# FPGA_-_Copy.net
KiCad netlist of a schematic drawn in Altium Designer
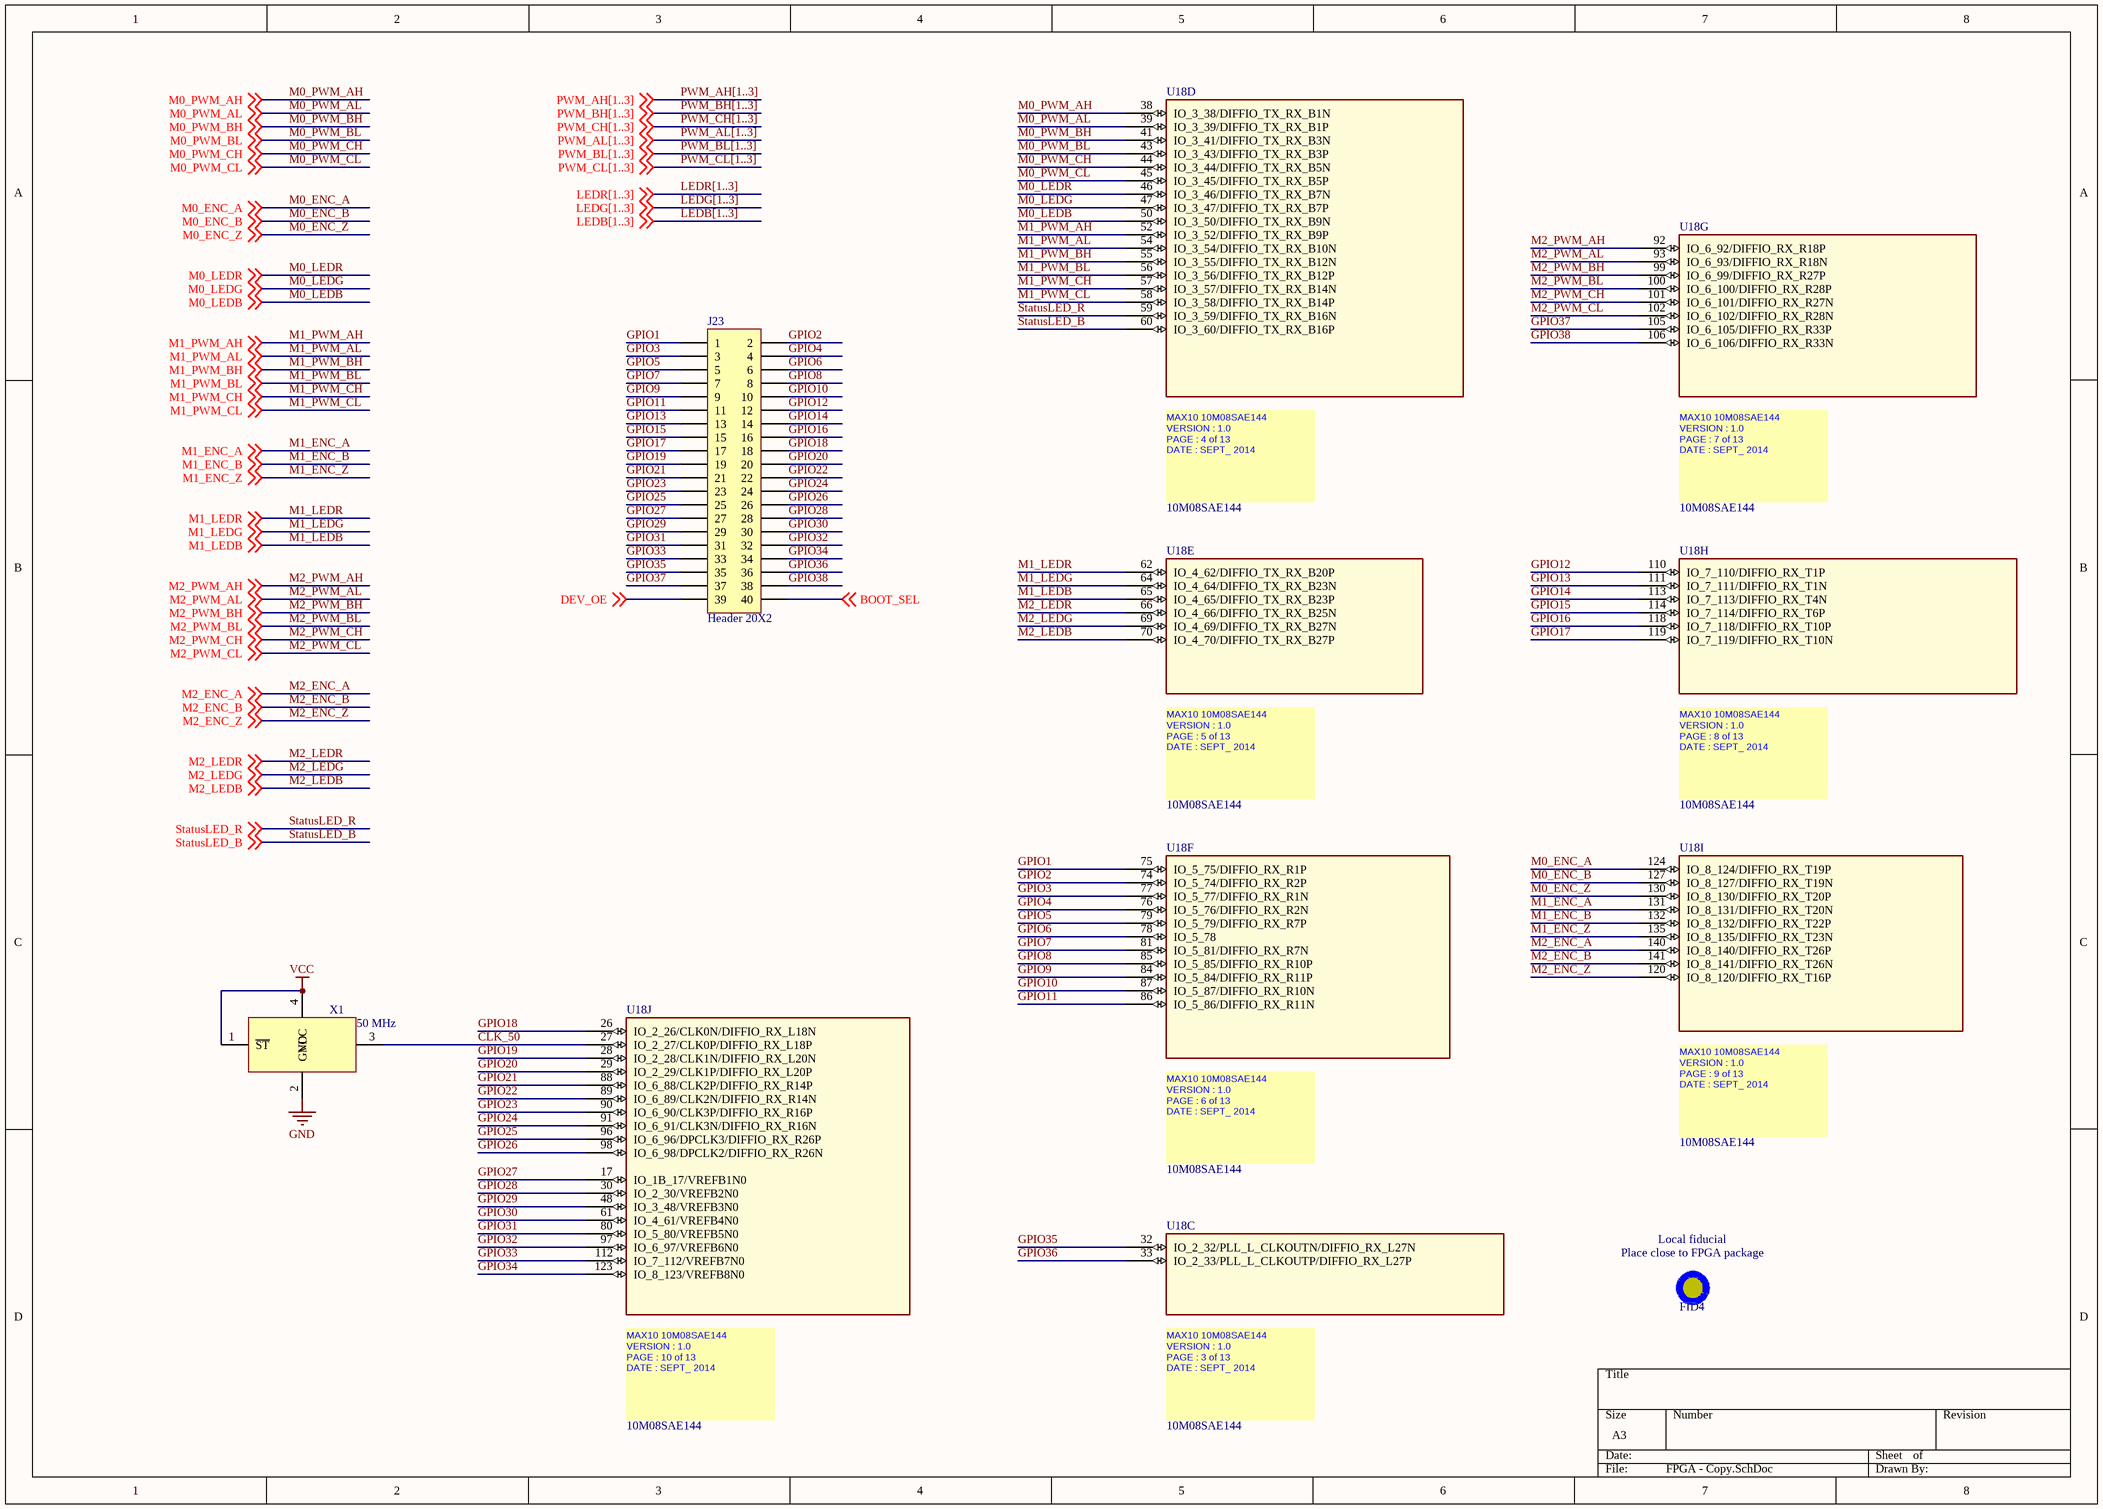
[diagram p0: FPGA - Copy.SchDoc]

(export (version "E")
  (design (tool "Eeschema 10.0.6"))
  (components
    (comp (ref "FID4")
      (value "FIDUCIAL")
      (footprint "FIDUCIAL")
      (description "1mm Fiducial with 2mm soldermask, 3mm keepout")
      (libsource (lib "CustomComponents") (part "FIDUCIAL"))
    )
    (comp (ref "J23")
      (value "Header 20X2")
      (footprint "HDR2X20")
      (description "Header, 20-Pin, Dual row")
      (fields (field (name "PUBLISHER") "Altium Limited"))
      (libsource (lib "Miscellaneous Connectors") (part "Header 20X2"))
    )
    (comp (ref "U18")
      (value "10M08SAE144")
      (footprint "SQFP50P2200X2200X165_HS-145N")
      (libsource (lib "10M08SAREVERSIONTEST_Library") (part "10M08SAE144"))
    )
    (comp (ref "X1")
      (value "50 MHz")
      (footprint "SPXO SG-210STF")
      (description "OSCILLATOR, SPXO, SG-210STF, 50 MHZ, SMD")
      (fields (field (name "Comment") "X1G0041710047"))
      (libsource (lib "CustomComponents") (part "X1G0041710047"))
    )
  )
  (nets
    (net (code "1") (name "/CLK_50") (class "Default")
      (node (ref "U18") (pin "27") (pinfunction "IO_2_27/CLK0P/DIFFIO_RX_L18P_27") (pintype "bidirectional"))
      (node (ref "X1") (pin "3") (pinfunction "CLKout_3") (pintype "passive"))
    )
    (net (code "2") (name "/GPIO1") (class "Default")
      (node (ref "J23") (pin "1") (pinfunction "1_1") (pintype "passive"))
      (node (ref "U18") (pin "75") (pinfunction "IO_5_75/DIFFIO_RX_R1P_75") (pintype "bidirectional"))
    )
    (net (code "3") (name "/GPIO2") (class "Default")
      (node (ref "J23") (pin "2") (pinfunction "2_2") (pintype "passive"))
      (node (ref "U18") (pin "74") (pinfunction "IO_5_74/DIFFIO_RX_R2P_74") (pintype "bidirectional"))
    )
    (net (code "4") (name "/GPIO3") (class "Default")
      (node (ref "J23") (pin "3") (pinfunction "3_3") (pintype "passive"))
      (node (ref "U18") (pin "77") (pinfunction "IO_5_77/DIFFIO_RX_R1N_77") (pintype "bidirectional"))
    )
    (net (code "5") (name "/GPIO4") (class "Default")
      (node (ref "J23") (pin "4") (pinfunction "4_4") (pintype "passive"))
      (node (ref "U18") (pin "76") (pinfunction "IO_5_76/DIFFIO_RX_R2N_76") (pintype "bidirectional"))
    )
    (net (code "6") (name "/GPIO5") (class "Default")
      (node (ref "J23") (pin "5") (pinfunction "5_5") (pintype "passive"))
      (node (ref "U18") (pin "79") (pinfunction "IO_5_79/DIFFIO_RX_R7P_79") (pintype "bidirectional"))
    )
    (net (code "7") (name "/GPIO6") (class "Default")
      (node (ref "J23") (pin "6") (pinfunction "6_6") (pintype "passive"))
      (node (ref "U18") (pin "78") (pinfunction "IO_5_78_78") (pintype "bidirectional"))
    )
    (net (code "8") (name "/GPIO7") (class "Default")
      (node (ref "J23") (pin "7") (pinfunction "7_7") (pintype "passive"))
      (node (ref "U18") (pin "81") (pinfunction "IO_5_81/DIFFIO_RX_R7N_81") (pintype "bidirectional"))
    )
    (net (code "9") (name "/GPIO8") (class "Default")
      (node (ref "J23") (pin "8") (pinfunction "8_8") (pintype "passive"))
      (node (ref "U18") (pin "85") (pinfunction "IO_5_85/DIFFIO_RX_R10P_85") (pintype "bidirectional"))
    )
    (net (code "10") (name "/GPIO9") (class "Default")
      (node (ref "J23") (pin "9") (pinfunction "9_9") (pintype "passive"))
      (node (ref "U18") (pin "84") (pinfunction "IO_5_84/DIFFIO_RX_R11P_84") (pintype "bidirectional"))
    )
    (net (code "11") (name "/GPIO10") (class "Default")
      (node (ref "J23") (pin "10") (pinfunction "10_10") (pintype "passive"))
      (node (ref "U18") (pin "87") (pinfunction "IO_5_87/DIFFIO_RX_R10N_87") (pintype "bidirectional"))
    )
    (net (code "12") (name "/GPIO11") (class "Default")
      (node (ref "J23") (pin "11") (pinfunction "11_11") (pintype "passive"))
      (node (ref "U18") (pin "86") (pinfunction "IO_5_86/DIFFIO_RX_R11N_86") (pintype "bidirectional"))
    )
    (net (code "13") (name "/GPIO12") (class "Default")
      (node (ref "J23") (pin "12") (pinfunction "12_12") (pintype "passive"))
      (node (ref "U18") (pin "110") (pinfunction "IO_7_110/DIFFIO_RX_T1P_110") (pintype "bidirectional"))
    )
    (net (code "14") (name "/GPIO13") (class "Default")
      (node (ref "J23") (pin "13") (pinfunction "13_13") (pintype "passive"))
      (node (ref "U18") (pin "111") (pinfunction "IO_7_111/DIFFIO_RX_T1N_111") (pintype "bidirectional"))
    )
    (net (code "15") (name "/GPIO14") (class "Default")
      (node (ref "J23") (pin "14") (pinfunction "14_14") (pintype "passive"))
      (node (ref "U18") (pin "113") (pinfunction "IO_7_113/DIFFIO_RX_T4N_113") (pintype "bidirectional"))
    )
    (net (code "16") (name "/GPIO15") (class "Default")
      (node (ref "J23") (pin "15") (pinfunction "15_15") (pintype "passive"))
      (node (ref "U18") (pin "114") (pinfunction "IO_7_114/DIFFIO_RX_T6P_114") (pintype "bidirectional"))
    )
    (net (code "17") (name "/GPIO16") (class "Default")
      (node (ref "J23") (pin "16") (pinfunction "16_16") (pintype "passive"))
      (node (ref "U18") (pin "118") (pinfunction "IO_7_118/DIFFIO_RX_T10P_118") (pintype "bidirectional"))
    )
    (net (code "18") (name "/GPIO17") (class "Default")
      (node (ref "J23") (pin "17") (pinfunction "17_17") (pintype "passive"))
      (node (ref "U18") (pin "119") (pinfunction "IO_7_119/DIFFIO_RX_T10N_119") (pintype "bidirectional"))
    )
    (net (code "19") (name "/GPIO18") (class "Default")
      (node (ref "J23") (pin "18") (pinfunction "18_18") (pintype "passive"))
      (node (ref "U18") (pin "26") (pinfunction "IO_2_26/CLK0N/DIFFIO_RX_L18N_26") (pintype "bidirectional"))
    )
    (net (code "20") (name "/GPIO19") (class "Default")
      (node (ref "J23") (pin "19") (pinfunction "19_19") (pintype "passive"))
      (node (ref "U18") (pin "28") (pinfunction "IO_2_28/CLK1N/DIFFIO_RX_L20N_28") (pintype "bidirectional"))
    )
    (net (code "21") (name "/GPIO20") (class "Default")
      (node (ref "J23") (pin "20") (pinfunction "20_20") (pintype "passive"))
      (node (ref "U18") (pin "29") (pinfunction "IO_2_29/CLK1P/DIFFIO_RX_L20P_29") (pintype "bidirectional"))
    )
    (net (code "22") (name "/GPIO21") (class "Default")
      (node (ref "J23") (pin "21") (pinfunction "21_21") (pintype "passive"))
      (node (ref "U18") (pin "88") (pinfunction "IO_6_88/CLK2P/DIFFIO_RX_R14P_88") (pintype "bidirectional"))
    )
    (net (code "23") (name "/GPIO22") (class "Default")
      (node (ref "J23") (pin "22") (pinfunction "22_22") (pintype "passive"))
      (node (ref "U18") (pin "89") (pinfunction "IO_6_89/CLK2N/DIFFIO_RX_R14N_89") (pintype "bidirectional"))
    )
    (net (code "24") (name "/GPIO23") (class "Default")
      (node (ref "J23") (pin "23") (pinfunction "23_23") (pintype "passive"))
      (node (ref "U18") (pin "90") (pinfunction "IO_6_90/CLK3P/DIFFIO_RX_R16P_90") (pintype "bidirectional"))
    )
    (net (code "25") (name "/GPIO24") (class "Default")
      (node (ref "J23") (pin "24") (pinfunction "24_24") (pintype "passive"))
      (node (ref "U18") (pin "91") (pinfunction "IO_6_91/CLK3N/DIFFIO_RX_R16N_91") (pintype "bidirectional"))
    )
    (net (code "26") (name "/GPIO25") (class "Default")
      (node (ref "J23") (pin "25") (pinfunction "25_25") (pintype "passive"))
      (node (ref "U18") (pin "96") (pinfunction "IO_6_96/DPCLK3/DIFFIO_RX_R26P_96") (pintype "bidirectional"))
    )
    (net (code "27") (name "/GPIO26") (class "Default")
      (node (ref "J23") (pin "26") (pinfunction "26_26") (pintype "passive"))
      (node (ref "U18") (pin "98") (pinfunction "IO_6_98/DPCLK2/DIFFIO_RX_R26N_98") (pintype "bidirectional"))
    )
    (net (code "28") (name "/GPIO27") (class "Default")
      (node (ref "J23") (pin "27") (pinfunction "27_27") (pintype "passive"))
      (node (ref "U18") (pin "17") (pinfunction "IO_1B_17/VREFB1N0_17") (pintype "bidirectional"))
    )
    (net (code "29") (name "/GPIO28") (class "Default")
      (node (ref "J23") (pin "28") (pinfunction "28_28") (pintype "passive"))
      (node (ref "U18") (pin "30") (pinfunction "IO_2_30/VREFB2N0_30") (pintype "bidirectional"))
    )
    (net (code "30") (name "/GPIO29") (class "Default")
      (node (ref "J23") (pin "29") (pinfunction "29_29") (pintype "passive"))
      (node (ref "U18") (pin "48") (pinfunction "IO_3_48/VREFB3N0_48") (pintype "bidirectional"))
    )
    (net (code "31") (name "/GPIO30") (class "Default")
      (node (ref "J23") (pin "30") (pinfunction "30_30") (pintype "passive"))
      (node (ref "U18") (pin "61") (pinfunction "IO_4_61/VREFB4N0_61") (pintype "bidirectional"))
    )
    (net (code "32") (name "/GPIO31") (class "Default")
      (node (ref "J23") (pin "31") (pinfunction "31_31") (pintype "passive"))
      (node (ref "U18") (pin "80") (pinfunction "IO_5_80/VREFB5N0_80") (pintype "bidirectional"))
    )
    (net (code "33") (name "/GPIO32") (class "Default")
      (node (ref "J23") (pin "32") (pinfunction "32_32") (pintype "passive"))
      (node (ref "U18") (pin "97") (pinfunction "IO_6_97/VREFB6N0_97") (pintype "bidirectional"))
    )
    (net (code "34") (name "/GPIO33") (class "Default")
      (node (ref "J23") (pin "33") (pinfunction "33_33") (pintype "passive"))
      (node (ref "U18") (pin "112") (pinfunction "IO_7_112/VREFB7N0_112") (pintype "bidirectional"))
    )
    (net (code "35") (name "/GPIO34") (class "Default")
      (node (ref "J23") (pin "34") (pinfunction "34_34") (pintype "passive"))
      (node (ref "U18") (pin "123") (pinfunction "IO_8_123/VREFB8N0_123") (pintype "bidirectional"))
    )
    (net (code "36") (name "/GPIO35") (class "Default")
      (node (ref "J23") (pin "35") (pinfunction "35_35") (pintype "passive"))
      (node (ref "U18") (pin "32") (pinfunction "IO_2_32/PLL_L_CLKOUTN/DIFFIO_RX_L27N_32") (pintype "bidirectional"))
    )
    (net (code "37") (name "/GPIO36") (class "Default")
      (node (ref "J23") (pin "36") (pinfunction "36_36") (pintype "passive"))
      (node (ref "U18") (pin "33") (pinfunction "IO_2_33/PLL_L_CLKOUTP/DIFFIO_RX_L27P_33") (pintype "bidirectional"))
    )
    (net (code "38") (name "/GPIO37") (class "Default")
      (node (ref "J23") (pin "37") (pinfunction "37_37") (pintype "passive"))
      (node (ref "U18") (pin "105") (pinfunction "IO_6_105/DIFFIO_RX_R33P_105") (pintype "bidirectional"))
    )
    (net (code "39") (name "/GPIO38") (class "Default")
      (node (ref "J23") (pin "38") (pinfunction "38_38") (pintype "passive"))
      (node (ref "U18") (pin "106") (pinfunction "IO_6_106/DIFFIO_RX_R33N_106") (pintype "bidirectional"))
    )
    (net (code "40") (name "BOOT_SEL") (class "Default")
      (node (ref "J23") (pin "40") (pinfunction "40_40") (pintype "passive"))
    )
    (net (code "41") (name "DEV_OE") (class "Default")
      (node (ref "J23") (pin "39") (pinfunction "39_39") (pintype "passive"))
    )
    (net (code "42") (name "GND") (class "Default")
      (node (ref "X1") (pin "2") (pinfunction "GND_2") (pintype "passive"))
    )
    (net (code "46") (name "M0_ENC_A") (class "Default")
      (node (ref "U18") (pin "124") (pinfunction "IO_8_124/DIFFIO_RX_T19P_124") (pintype "bidirectional"))
    )
    (net (code "47") (name "M0_ENC_B") (class "Default")
      (node (ref "U18") (pin "127") (pinfunction "IO_8_127/DIFFIO_RX_T19N_127") (pintype "bidirectional"))
    )
    (net (code "48") (name "M0_ENC_Z") (class "Default")
      (node (ref "U18") (pin "130") (pinfunction "IO_8_130/DIFFIO_RX_T20P_130") (pintype "bidirectional"))
    )
    (net (code "49") (name "M0_LEDB") (class "Default")
      (node (ref "U18") (pin "50") (pinfunction "IO_3_50/DIFFIO_TX_RX_B9N_50") (pintype "bidirectional"))
    )
    (net (code "50") (name "M0_LEDG") (class "Default")
      (node (ref "U18") (pin "47") (pinfunction "IO_3_47/DIFFIO_TX_RX_B7P_47") (pintype "bidirectional"))
    )
    (net (code "51") (name "M0_LEDR") (class "Default")
      (node (ref "U18") (pin "46") (pinfunction "IO_3_46/DIFFIO_TX_RX_B7N_46") (pintype "bidirectional"))
    )
    (net (code "52") (name "M0_PWM_AH") (class "Default")
      (node (ref "U18") (pin "38") (pinfunction "IO_3_38/DIFFIO_TX_RX_B1N_38") (pintype "bidirectional"))
    )
    (net (code "53") (name "M0_PWM_AL") (class "Default")
      (node (ref "U18") (pin "39") (pinfunction "IO_3_39/DIFFIO_TX_RX_B1P_39") (pintype "bidirectional"))
    )
    (net (code "54") (name "M0_PWM_BH") (class "Default")
      (node (ref "U18") (pin "41") (pinfunction "IO_3_41/DIFFIO_TX_RX_B3N_41") (pintype "bidirectional"))
    )
    (net (code "55") (name "M0_PWM_BL") (class "Default")
      (node (ref "U18") (pin "43") (pinfunction "IO_3_43/DIFFIO_TX_RX_B3P_43") (pintype "bidirectional"))
    )
    (net (code "56") (name "M0_PWM_CH") (class "Default")
      (node (ref "U18") (pin "44") (pinfunction "IO_3_44/DIFFIO_TX_RX_B5N_44") (pintype "bidirectional"))
    )
    (net (code "57") (name "M0_PWM_CL") (class "Default")
      (node (ref "U18") (pin "45") (pinfunction "IO_3_45/DIFFIO_TX_RX_B5P_45") (pintype "bidirectional"))
    )
    (net (code "58") (name "M1_ENC_A") (class "Default")
      (node (ref "U18") (pin "131") (pinfunction "IO_8_131/DIFFIO_RX_T20N_131") (pintype "bidirectional"))
    )
    (net (code "59") (name "M1_ENC_B") (class "Default")
      (node (ref "U18") (pin "132") (pinfunction "IO_8_132/DIFFIO_RX_T22P_132") (pintype "bidirectional"))
    )
    (net (code "60") (name "M1_ENC_Z") (class "Default")
      (node (ref "U18") (pin "135") (pinfunction "IO_8_135/DIFFIO_RX_T23N_135") (pintype "bidirectional"))
    )
    (net (code "61") (name "M1_LEDB") (class "Default")
      (node (ref "U18") (pin "65") (pinfunction "IO_4_65/DIFFIO_TX_RX_B23P_65") (pintype "bidirectional"))
    )
    (net (code "62") (name "M1_LEDG") (class "Default")
      (node (ref "U18") (pin "64") (pinfunction "IO_4_64/DIFFIO_TX_RX_B23N_64") (pintype "bidirectional"))
    )
    (net (code "63") (name "M1_LEDR") (class "Default")
      (node (ref "U18") (pin "62") (pinfunction "IO_4_62/DIFFIO_TX_RX_B20P_62") (pintype "bidirectional"))
    )
    (net (code "64") (name "M1_PWM_AH") (class "Default")
      (node (ref "U18") (pin "52") (pinfunction "IO_3_52/DIFFIO_TX_RX_B9P_52") (pintype "bidirectional"))
    )
    (net (code "65") (name "M1_PWM_AL") (class "Default")
      (node (ref "U18") (pin "54") (pinfunction "IO_3_54/DIFFIO_TX_RX_B10N_54") (pintype "bidirectional"))
    )
    (net (code "66") (name "M1_PWM_BH") (class "Default")
      (node (ref "U18") (pin "55") (pinfunction "IO_3_55/DIFFIO_TX_RX_B12N_55") (pintype "bidirectional"))
    )
    (net (code "67") (name "M1_PWM_BL") (class "Default")
      (node (ref "U18") (pin "56") (pinfunction "IO_3_56/DIFFIO_TX_RX_B12P_56") (pintype "bidirectional"))
    )
    (net (code "68") (name "M1_PWM_CH") (class "Default")
      (node (ref "U18") (pin "57") (pinfunction "IO_3_57/DIFFIO_TX_RX_B14N_57") (pintype "bidirectional"))
    )
    (net (code "69") (name "M1_PWM_CL") (class "Default")
      (node (ref "U18") (pin "58") (pinfunction "IO_3_58/DIFFIO_TX_RX_B14P_58") (pintype "bidirectional"))
    )
    (net (code "70") (name "M2_ENC_A") (class "Default")
      (node (ref "U18") (pin "140") (pinfunction "IO_8_140/DIFFIO_RX_T26P_140") (pintype "bidirectional"))
    )
    (net (code "71") (name "M2_ENC_B") (class "Default")
      (node (ref "U18") (pin "141") (pinfunction "IO_8_141/DIFFIO_RX_T26N_141") (pintype "bidirectional"))
    )
    (net (code "72") (name "M2_ENC_Z") (class "Default")
      (node (ref "U18") (pin "120") (pinfunction "IO_8_120/DIFFIO_RX_T16P_120") (pintype "bidirectional"))
    )
    (net (code "73") (name "M2_LEDB") (class "Default")
      (node (ref "U18") (pin "70") (pinfunction "IO_4_70/DIFFIO_TX_RX_B27P_70") (pintype "bidirectional"))
    )
    (net (code "74") (name "M2_LEDG") (class "Default")
      (node (ref "U18") (pin "69") (pinfunction "IO_4_69/DIFFIO_TX_RX_B27N_69") (pintype "bidirectional"))
    )
    (net (code "75") (name "M2_LEDR") (class "Default")
      (node (ref "U18") (pin "66") (pinfunction "IO_4_66/DIFFIO_TX_RX_B25N_66") (pintype "bidirectional"))
    )
    (net (code "76") (name "M2_PWM_AH") (class "Default")
      (node (ref "U18") (pin "92") (pinfunction "IO_6_92/DIFFIO_RX_R18P_92") (pintype "bidirectional"))
    )
    (net (code "77") (name "M2_PWM_AL") (class "Default")
      (node (ref "U18") (pin "93") (pinfunction "IO_6_93/DIFFIO_RX_R18N_93") (pintype "bidirectional"))
    )
    (net (code "78") (name "M2_PWM_BH") (class "Default")
      (node (ref "U18") (pin "99") (pinfunction "IO_6_99/DIFFIO_RX_R27P_99") (pintype "bidirectional"))
    )
    (net (code "79") (name "M2_PWM_BL") (class "Default")
      (node (ref "U18") (pin "100") (pinfunction "IO_6_100/DIFFIO_RX_R28P_100") (pintype "bidirectional"))
    )
    (net (code "80") (name "M2_PWM_CH") (class "Default")
      (node (ref "U18") (pin "101") (pinfunction "IO_6_101/DIFFIO_RX_R27N_101") (pintype "bidirectional"))
    )
    (net (code "81") (name "M2_PWM_CL") (class "Default")
      (node (ref "U18") (pin "102") (pinfunction "IO_6_102/DIFFIO_RX_R28N_102") (pintype "bidirectional"))
    )
    (net (code "88") (name "StatusLED_B") (class "Default")
      (node (ref "U18") (pin "60") (pinfunction "IO_3_60/DIFFIO_TX_RX_B16P_60") (pintype "bidirectional"))
    )
    (net (code "89") (name "StatusLED_R") (class "Default")
      (node (ref "U18") (pin "59") (pinfunction "IO_3_59/DIFFIO_TX_RX_B16N_59") (pintype "bidirectional"))
    )
    (net (code "90") (name "VCC") (class "Default")
      (node (ref "X1") (pin "1") (pinfunction "~{ST}_1") (pintype "passive"))
      (node (ref "X1") (pin "4") (pinfunction "VCC_4") (pintype "passive"))
    )
  )
)
